# main.net
KiCad netlist of a schematic drawn in EAGLE
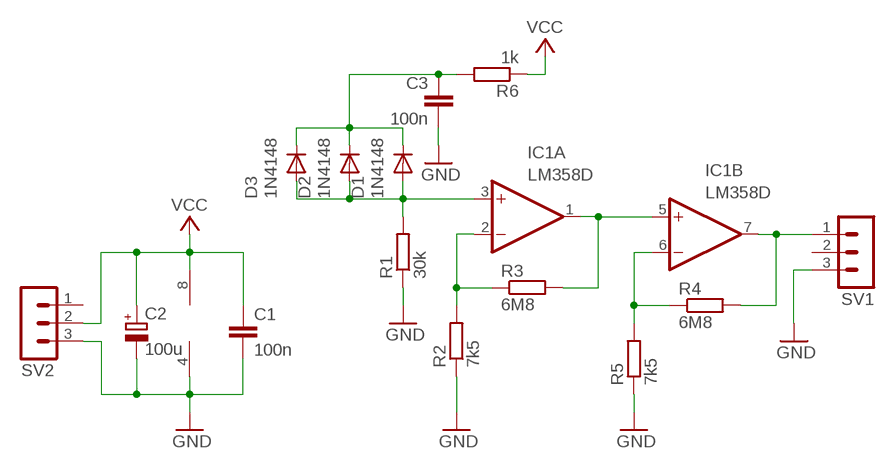
[diagram p0: schematic, sheet 1]

(export (version "E")
  (design (tool "Eeschema 10.0.6"))
  (components
    (comp (ref "C1")
      (value "100n")
      (footprint "eagle-import:C1608")
      (libsource (lib "eagle-import") (part "C-EUC1608"))
    )
    (comp (ref "C2")
      (value "100u")
      (footprint "eagle-import:E2,5-5")
      (libsource (lib "eagle-import") (part "CPOL-EUE2.5-5"))
    )
    (comp (ref "C3")
      (value "100n")
      (footprint "eagle-import:C1608")
      (libsource (lib "eagle-import") (part "C-EUC1608"))
    )
    (comp (ref "D1")
      (value "1N4148")
      (footprint "eagle-import:DO35-7")
      (libsource (lib "eagle-import") (part "1N4148DO35-7"))
    )
    (comp (ref "D2")
      (value "1N4148")
      (footprint "eagle-import:DO35-7")
      (libsource (lib "eagle-import") (part "1N4148DO35-7"))
    )
    (comp (ref "D3")
      (value "1N4148")
      (footprint "eagle-import:DO35-7")
      (libsource (lib "eagle-import") (part "1N4148DO35-7"))
    )
    (comp (ref "IC1")
      (value "LM358D")
      (footprint "eagle-import:SO08")
      (libsource (lib "eagle-import") (part "LM358D"))
    )
    (comp (ref "R1")
      (value "30k")
      (footprint "eagle-import:0204V")
      (libsource (lib "eagle-import") (part "R-EU_0204/2V"))
    )
    (comp (ref "R2")
      (value "7k5")
      (footprint "eagle-import:0204V")
      (libsource (lib "eagle-import") (part "R-EU_0204/2V"))
    )
    (comp (ref "R3")
      (value "6M8")
      (footprint "eagle-import:0204V")
      (libsource (lib "eagle-import") (part "R-EU_0204/2V"))
    )
    (comp (ref "R4")
      (value "6M8")
      (footprint "eagle-import:0204V")
      (libsource (lib "eagle-import") (part "R-EU_0204/2V"))
    )
    (comp (ref "R5")
      (value "7k5")
      (footprint "eagle-import:0204V")
      (libsource (lib "eagle-import") (part "R-EU_0204/2V"))
    )
    (comp (ref "R6")
      (value "1k")
      (footprint "eagle-import:0204V")
      (libsource (lib "eagle-import") (part "R-EU_0204/2V"))
    )
    (comp (ref "SV1")
      (value "MA03-1")
      (footprint "eagle-import:MA03-1")
      (libsource (lib "eagle-import") (part "MA03-1"))
    )
    (comp (ref "SV2")
      (value "MA03-1")
      (footprint "eagle-import:MA03-1")
      (libsource (lib "eagle-import") (part "MA03-1"))
    )
  )
  (nets
    (net (code "1") (name "GND") (class "Default")
      (node (ref "C1") (pin "2") (pinfunction "2_2") (pintype "passive"))
      (node (ref "C2") (pin "-") (pinfunction "-_-") (pintype "passive"))
      (node (ref "C3") (pin "2") (pinfunction "2_2") (pintype "passive"))
      (node (ref "IC1") (pin "4") (pinfunction "V-_4") (pintype "power_in"))
      (node (ref "R1") (pin "1") (pinfunction "1_1") (pintype "passive"))
      (node (ref "R2") (pin "1") (pinfunction "1_1") (pintype "passive"))
      (node (ref "R5") (pin "1") (pinfunction "1_1") (pintype "passive"))
      (node (ref "SV1") (pin "3") (pinfunction "3_3") (pintype "passive"))
      (node (ref "SV2") (pin "3") (pinfunction "3_3") (pintype "passive"))
    )
    (net (code "2") (name "Net-(C3-Pad1)") (class "Default")
      (node (ref "C3") (pin "1") (pinfunction "1_1") (pintype "passive"))
      (node (ref "D1") (pin "C") (pinfunction "C_C") (pintype "passive"))
      (node (ref "D2") (pin "C") (pinfunction "C_C") (pintype "passive"))
      (node (ref "D3") (pin "C") (pinfunction "C_C") (pintype "passive"))
      (node (ref "R6") (pin "2") (pinfunction "2_2") (pintype "passive"))
    )
    (net (code "3") (name "Net-(IC1A-+IN)") (class "Default")
      (node (ref "D1") (pin "A") (pinfunction "A_A") (pintype "passive"))
      (node (ref "D2") (pin "A") (pinfunction "A_A") (pintype "passive"))
      (node (ref "D3") (pin "A") (pinfunction "A_A") (pintype "passive"))
      (node (ref "IC1") (pin "3") (pinfunction "+IN_3") (pintype "input"))
      (node (ref "R1") (pin "2") (pinfunction "2_2") (pintype "passive"))
    )
    (net (code "4") (name "Net-(IC1A--IN)") (class "Default")
      (node (ref "IC1") (pin "2") (pinfunction "-IN_2") (pintype "input"))
      (node (ref "R2") (pin "2") (pinfunction "2_2") (pintype "passive"))
      (node (ref "R3") (pin "1") (pinfunction "1_1") (pintype "passive"))
    )
    (net (code "5") (name "Net-(IC1A-OUT)") (class "Default")
      (node (ref "IC1") (pin "1") (pinfunction "OUT_1") (pintype "output"))
      (node (ref "IC1") (pin "5") (pinfunction "+IN_5") (pintype "input"))
      (node (ref "R3") (pin "2") (pinfunction "2_2") (pintype "passive"))
    )
    (net (code "6") (name "Net-(IC1B--IN)") (class "Default")
      (node (ref "IC1") (pin "6") (pinfunction "-IN_6") (pintype "input"))
      (node (ref "R4") (pin "1") (pinfunction "1_1") (pintype "passive"))
      (node (ref "R5") (pin "2") (pinfunction "2_2") (pintype "passive"))
    )
    (net (code "7") (name "Net-(IC1B-OUT)") (class "Default")
      (node (ref "IC1") (pin "7") (pinfunction "OUT_7") (pintype "output"))
      (node (ref "R4") (pin "2") (pinfunction "2_2") (pintype "passive"))
      (node (ref "SV1") (pin "1") (pinfunction "1_1") (pintype "passive"))
    )
    (net (code "8") (name "VCC") (class "Default")
      (node (ref "C1") (pin "1") (pinfunction "1_1") (pintype "passive"))
      (node (ref "C2") (pin "+") (pinfunction "+_+") (pintype "passive"))
      (node (ref "IC1") (pin "8") (pinfunction "V+_8") (pintype "power_in"))
      (node (ref "R6") (pin "1") (pinfunction "1_1") (pintype "passive"))
      (node (ref "SV2") (pin "2") (pinfunction "2_2") (pintype "passive"))
    )
    (net (code "9") (name "unconnected-(SV1-Pad2)") (class "Default")
      (node (ref "SV1") (pin "2") (pinfunction "2_2") (pintype "passive"))
    )
    (net (code "10") (name "unconnected-(SV2-Pad1)") (class "Default")
      (node (ref "SV2") (pin "1") (pinfunction "1_1") (pintype "passive"))
    )
  )
)
